# atari2600-simplest-cart.net
KiCad netlist of a schematic drawn in EAGLE
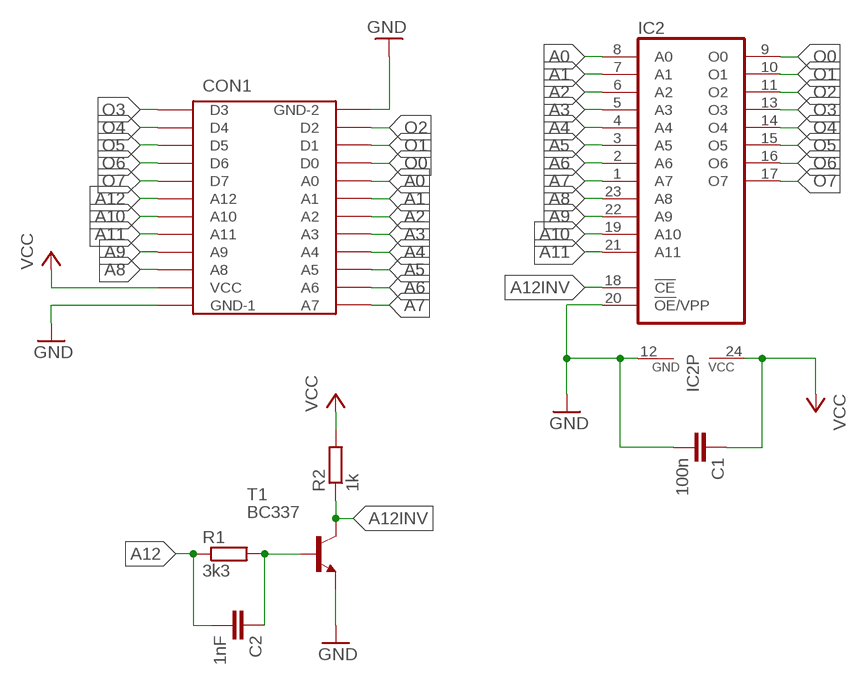
[diagram p0: schematic, sheet 1]

(export (version "E")
  (design (tool "Eeschema 10.0.6"))
  (components
    (comp (ref "C1")
      (value "100n")
      (footprint "eagle-import:C025-025X050")
      (libsource (lib "eagle-import") (part "C-EU025-025X050"))
    )
    (comp (ref "C2")
      (value "1nF")
      (footprint "eagle-import:C025-025X050")
      (libsource (lib "eagle-import") (part "C-EU025-025X050"))
    )
    (comp (ref "CON1")
      (value "24PINEDGE-ATARI-2600")
      (footprint "eagle-import:24PINEDGE-ATARI-2600")
      (libsource (lib "eagle-import") (part "24PINEDGE-ATARI-2600"))
    )
    (comp (ref "IC2")
      (value "2732")
      (footprint "eagle-import:DIL24")
      (libsource (lib "eagle-import") (part "2732"))
    )
    (comp (ref "R1")
      (value "3k3")
      (footprint "eagle-import:0204_7")
      (libsource (lib "eagle-import") (part "R-EU_0204/7"))
    )
    (comp (ref "R2")
      (value "1k")
      (footprint "eagle-import:0204_7")
      (libsource (lib "eagle-import") (part "R-EU_0204/7"))
    )
    (comp (ref "T1")
      (value "BC337")
      (footprint "eagle-import:TO92")
      (libsource (lib "eagle-import") (part "BC337"))
    )
  )
  (nets
    (net (code "1") (name "A0") (class "Default")
      (node (ref "CON1") (pin "20") (pinfunction "A0_20") (pintype "passive"))
      (node (ref "IC2") (pin "8") (pinfunction "A0_8") (pintype "input"))
    )
    (net (code "2") (name "A1") (class "Default")
      (node (ref "CON1") (pin "19") (pinfunction "A1_19") (pintype "passive"))
      (node (ref "IC2") (pin "7") (pinfunction "A1_7") (pintype "input"))
    )
    (net (code "3") (name "A2") (class "Default")
      (node (ref "CON1") (pin "18") (pinfunction "A2_18") (pintype "passive"))
      (node (ref "IC2") (pin "6") (pinfunction "A2_6") (pintype "input"))
    )
    (net (code "4") (name "A3") (class "Default")
      (node (ref "CON1") (pin "17") (pinfunction "A3_17") (pintype "passive"))
      (node (ref "IC2") (pin "5") (pinfunction "A3_5") (pintype "input"))
    )
    (net (code "5") (name "A4") (class "Default")
      (node (ref "CON1") (pin "16") (pinfunction "A4_16") (pintype "passive"))
      (node (ref "IC2") (pin "4") (pinfunction "A4_4") (pintype "input"))
    )
    (net (code "6") (name "A5") (class "Default")
      (node (ref "CON1") (pin "15") (pinfunction "A5_15") (pintype "passive"))
      (node (ref "IC2") (pin "3") (pinfunction "A5_3") (pintype "input"))
    )
    (net (code "7") (name "A6") (class "Default")
      (node (ref "CON1") (pin "14") (pinfunction "A6_14") (pintype "passive"))
      (node (ref "IC2") (pin "2") (pinfunction "A6_2") (pintype "input"))
    )
    (net (code "8") (name "A7") (class "Default")
      (node (ref "CON1") (pin "13") (pinfunction "A7_13") (pintype "passive"))
      (node (ref "IC2") (pin "1") (pinfunction "A7_1") (pintype "input"))
    )
    (net (code "9") (name "A8") (class "Default")
      (node (ref "CON1") (pin "10") (pinfunction "A8_10") (pintype "passive"))
      (node (ref "IC2") (pin "23") (pinfunction "A8_23") (pintype "input"))
    )
    (net (code "10") (name "A9") (class "Default")
      (node (ref "CON1") (pin "9") (pinfunction "A9_9") (pintype "passive"))
      (node (ref "IC2") (pin "22") (pinfunction "A9_22") (pintype "input"))
    )
    (net (code "11") (name "A10") (class "Default")
      (node (ref "CON1") (pin "7") (pinfunction "A10_7") (pintype "passive"))
      (node (ref "IC2") (pin "19") (pinfunction "A10_19") (pintype "input"))
    )
    (net (code "12") (name "A11") (class "Default")
      (node (ref "CON1") (pin "8") (pinfunction "A11_8") (pintype "passive"))
      (node (ref "IC2") (pin "21") (pinfunction "A11_21") (pintype "input"))
    )
    (net (code "13") (name "A12") (class "Default")
      (node (ref "C2") (pin "2") (pinfunction "2_2") (pintype "passive"))
      (node (ref "CON1") (pin "6") (pinfunction "A12_6") (pintype "passive"))
      (node (ref "R1") (pin "1") (pinfunction "1_1") (pintype "passive"))
    )
    (net (code "14") (name "A12INV") (class "Default")
      (node (ref "IC2") (pin "18") (pinfunction "~{CE}_18") (pintype "input"))
      (node (ref "R2") (pin "1") (pinfunction "1_1") (pintype "passive"))
      (node (ref "T1") (pin "3") (pinfunction "C_3") (pintype "passive"))
    )
    (net (code "15") (name "GND") (class "Default")
      (node (ref "C1") (pin "2") (pinfunction "2_2") (pintype "passive"))
      (node (ref "CON1") (pin "12") (pinfunction "GND-1_12") (pintype "passive"))
      (node (ref "CON1") (pin "24") (pinfunction "GND-2_24") (pintype "passive"))
      (node (ref "IC2") (pin "12") (pinfunction "GND_12") (pintype "power_in"))
      (node (ref "IC2") (pin "20") (pinfunction "~{OE}/VPP_20") (pintype "input"))
      (node (ref "T1") (pin "1") (pinfunction "E_1") (pintype "passive"))
    )
    (net (code "16") (name "Net-(T1-B)") (class "Default")
      (node (ref "C2") (pin "1") (pinfunction "1_1") (pintype "passive"))
      (node (ref "R1") (pin "2") (pinfunction "2_2") (pintype "passive"))
      (node (ref "T1") (pin "2") (pinfunction "B_2") (pintype "passive"))
    )
    (net (code "17") (name "O0") (class "Default")
      (node (ref "CON1") (pin "21") (pinfunction "D0_21") (pintype "passive"))
      (node (ref "IC2") (pin "9") (pinfunction "O0_9") (pintype "tri_state"))
    )
    (net (code "18") (name "O1") (class "Default")
      (node (ref "CON1") (pin "22") (pinfunction "D1_22") (pintype "passive"))
      (node (ref "IC2") (pin "10") (pinfunction "O1_10") (pintype "tri_state"))
    )
    (net (code "19") (name "O2") (class "Default")
      (node (ref "CON1") (pin "23") (pinfunction "D2_23") (pintype "passive"))
      (node (ref "IC2") (pin "11") (pinfunction "O2_11") (pintype "tri_state"))
    )
    (net (code "20") (name "O3") (class "Default")
      (node (ref "CON1") (pin "1") (pinfunction "D3_1") (pintype "passive"))
      (node (ref "IC2") (pin "13") (pinfunction "O3_13") (pintype "tri_state"))
    )
    (net (code "21") (name "O4") (class "Default")
      (node (ref "CON1") (pin "2") (pinfunction "D4_2") (pintype "passive"))
      (node (ref "IC2") (pin "14") (pinfunction "O4_14") (pintype "tri_state"))
    )
    (net (code "22") (name "O5") (class "Default")
      (node (ref "CON1") (pin "3") (pinfunction "D5_3") (pintype "passive"))
      (node (ref "IC2") (pin "15") (pinfunction "O5_15") (pintype "tri_state"))
    )
    (net (code "23") (name "O6") (class "Default")
      (node (ref "CON1") (pin "4") (pinfunction "D6_4") (pintype "passive"))
      (node (ref "IC2") (pin "16") (pinfunction "O6_16") (pintype "tri_state"))
    )
    (net (code "24") (name "O7") (class "Default")
      (node (ref "CON1") (pin "5") (pinfunction "D7_5") (pintype "passive"))
      (node (ref "IC2") (pin "17") (pinfunction "O7_17") (pintype "tri_state"))
    )
    (net (code "25") (name "VCC") (class "Default")
      (node (ref "C1") (pin "1") (pinfunction "1_1") (pintype "passive"))
      (node (ref "CON1") (pin "11") (pinfunction "VCC_11") (pintype "passive"))
      (node (ref "IC2") (pin "24") (pinfunction "VCC_24") (pintype "power_in"))
      (node (ref "R2") (pin "2") (pinfunction "2_2") (pintype "passive"))
    )
  )
)
